# Alarm_project.net
KiCad netlist of a schematic drawn in EAGLE
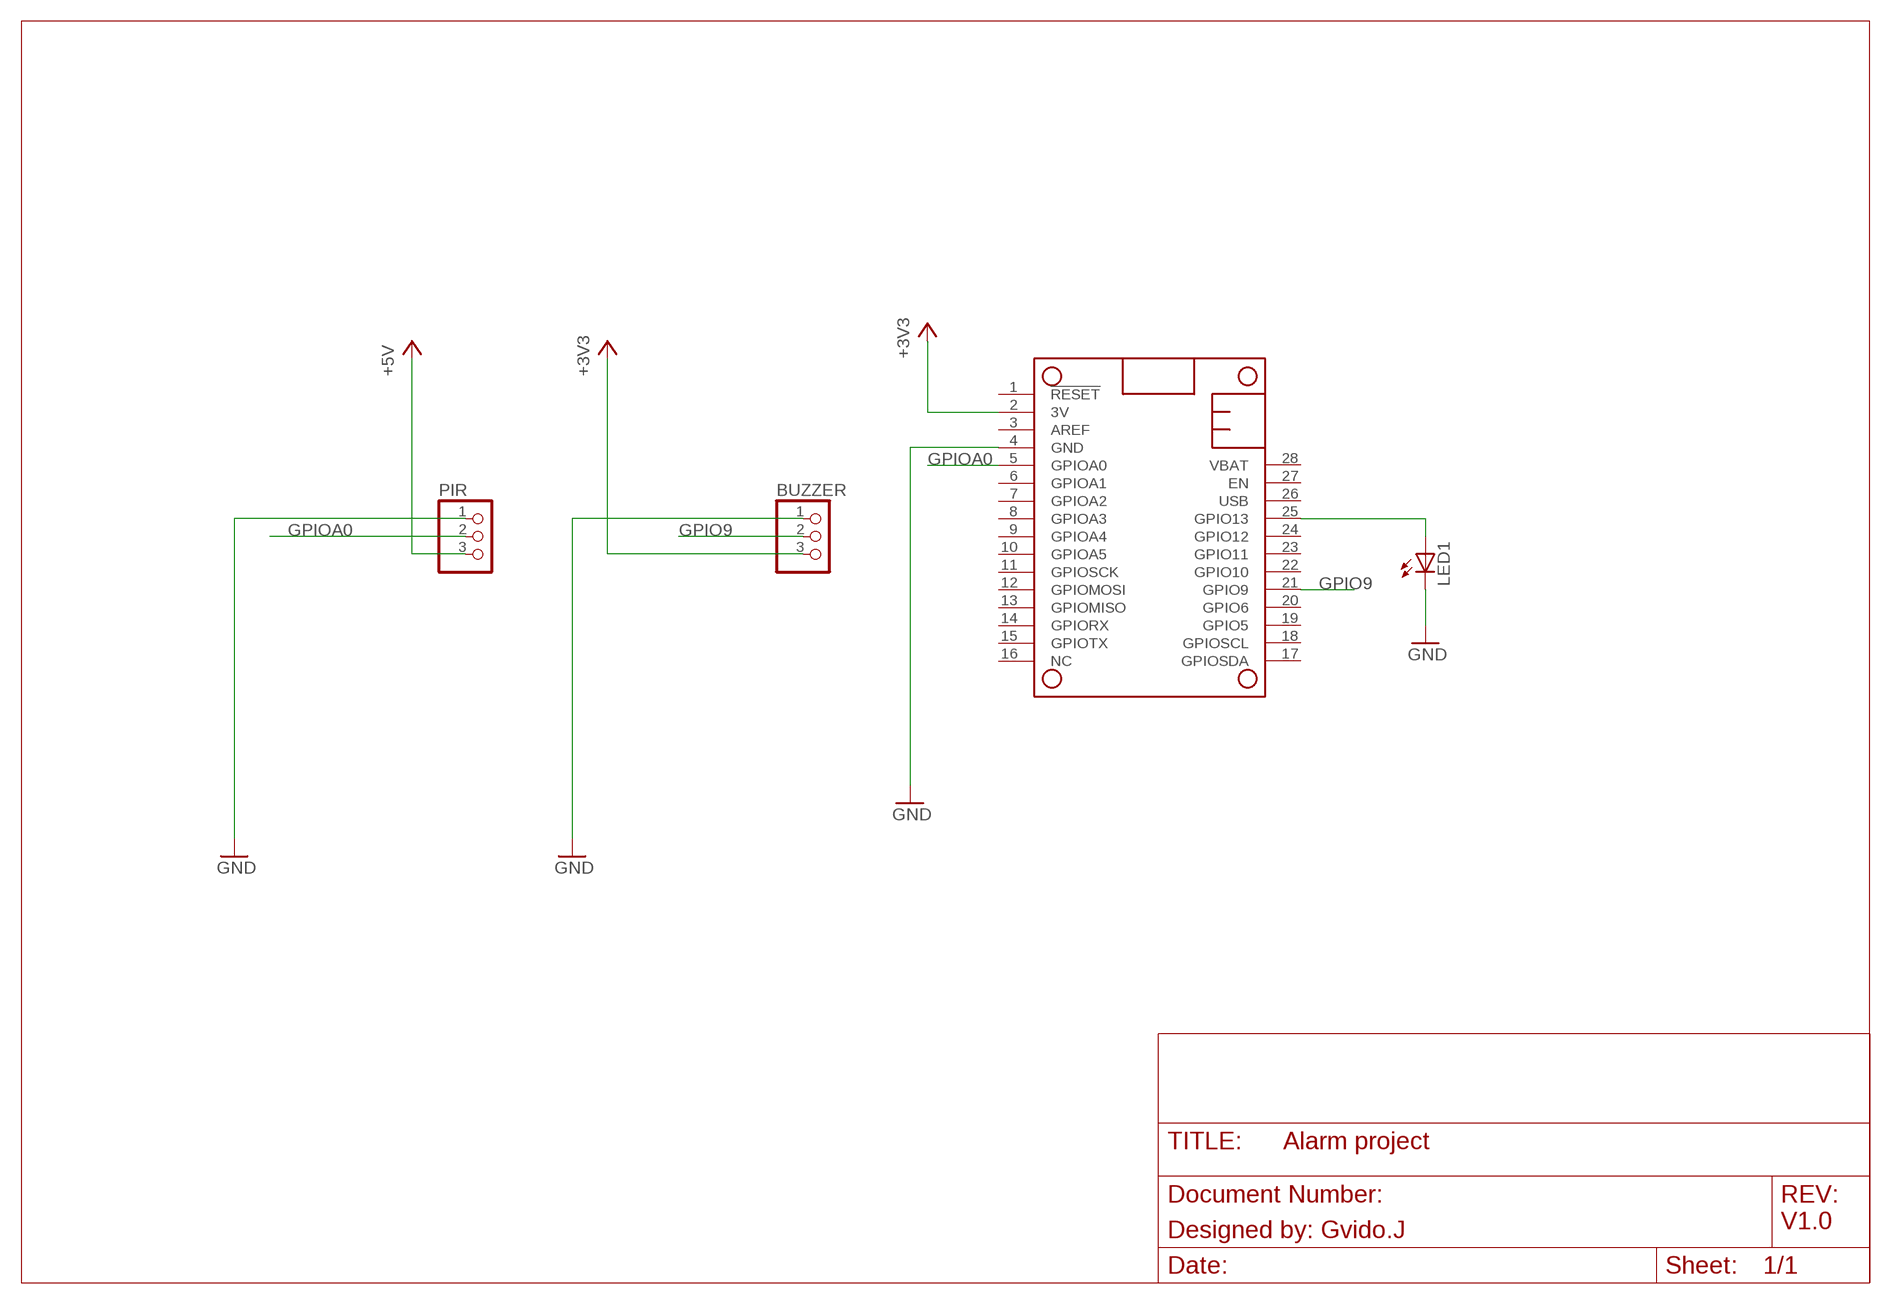
[diagram p0: schematic, sheet 1]

(export (version "E")
  (design (tool "Eeschema 10.0.6"))
  (components
    (comp (ref "BUZZER")
      (value "PINHD-1X3")
      (footprint "eagle-import:1X03")
      (libsource (lib "eagle-import") (part "PINHD-1X3"))
    )
    (comp (ref "LED1")
      (value "LED")
      (footprint "eagle-import:SMARTLED-TTW")
      (libsource (lib "eagle-import") (part "LED"))
    )
    (comp (ref "MS1")
      (value "FEATHERWING")
      (footprint "eagle-import:FEATHERWING")
      (libsource (lib "eagle-import") (part "FEATHERWING"))
    )
    (comp (ref "PIR")
      (value "PINHD-1X3")
      (footprint "eagle-import:1X03")
      (libsource (lib "eagle-import") (part "PINHD-1X3"))
    )
  )
  (nets
    (net (code "1") (name "+3V3") (class "Default")
      (node (ref "BUZZER") (pin "3") (pinfunction "3_3") (pintype "passive"))
      (node (ref "MS1") (pin "2") (pinfunction "3V_2") (pintype "power_in"))
    )
    (net (code "2") (name "+5V") (class "Default")
      (node (ref "PIR") (pin "3") (pinfunction "3_3") (pintype "passive"))
    )
    (net (code "3") (name "/GPIO9") (class "Default")
      (node (ref "BUZZER") (pin "2") (pinfunction "2_2") (pintype "passive"))
      (node (ref "MS1") (pin "21") (pinfunction "GPIO9_21") (pintype "bidirectional"))
    )
    (net (code "4") (name "/GPIOA0") (class "Default")
      (node (ref "MS1") (pin "5") (pinfunction "GPIOA0_5") (pintype "bidirectional"))
      (node (ref "PIR") (pin "2") (pinfunction "2_2") (pintype "passive"))
    )
    (net (code "5") (name "/USB") (class "Default")
      (node (ref "MS1") (pin "26") (pinfunction "USB_26") (pintype "power_in"))
    )
    (net (code "6") (name "/VBAT") (class "Default")
      (node (ref "MS1") (pin "28") (pinfunction "VBAT_28") (pintype "power_in"))
    )
    (net (code "7") (name "GND") (class "Default")
      (node (ref "BUZZER") (pin "1") (pinfunction "1_1") (pintype "passive"))
      (node (ref "LED1") (pin "C@1") (pinfunction "C_C@1") (pintype "passive"))
      (node (ref "MS1") (pin "4") (pinfunction "GND_4") (pintype "power_in"))
      (node (ref "PIR") (pin "1") (pinfunction "1_1") (pintype "passive"))
    )
    (net (code "8") (name "Net-(LED1-A)") (class "Default")
      (node (ref "LED1") (pin "A@1") (pinfunction "A_A@1") (pintype "passive"))
      (node (ref "MS1") (pin "25") (pinfunction "GPIO13_25") (pintype "bidirectional"))
    )
    (net (code "9") (name "unconnected-(MS1-AREF-Pad3)") (class "Default")
      (node (ref "MS1") (pin "3") (pinfunction "AREF_3") (pintype "passive"))
    )
    (net (code "10") (name "unconnected-(MS1-EN-Pad27)") (class "Default")
      (node (ref "MS1") (pin "27") (pinfunction "EN_27") (pintype "passive"))
    )
    (net (code "11") (name "unconnected-(MS1-GPIO5-Pad19)") (class "Default")
      (node (ref "MS1") (pin "19") (pinfunction "GPIO5_19") (pintype "bidirectional"))
    )
    (net (code "12") (name "unconnected-(MS1-GPIO6-Pad20)") (class "Default")
      (node (ref "MS1") (pin "20") (pinfunction "GPIO6_20") (pintype "bidirectional"))
    )
    (net (code "13") (name "unconnected-(MS1-GPIO10-Pad22)") (class "Default")
      (node (ref "MS1") (pin "22") (pinfunction "GPIO10_22") (pintype "bidirectional"))
    )
    (net (code "14") (name "unconnected-(MS1-GPIO11-Pad23)") (class "Default")
      (node (ref "MS1") (pin "23") (pinfunction "GPIO11_23") (pintype "bidirectional"))
    )
    (net (code "15") (name "unconnected-(MS1-GPIO12-Pad24)") (class "Default")
      (node (ref "MS1") (pin "24") (pinfunction "GPIO12_24") (pintype "bidirectional"))
    )
    (net (code "16") (name "unconnected-(MS1-GPIOA1-Pad6)") (class "Default")
      (node (ref "MS1") (pin "6") (pinfunction "GPIOA1_6") (pintype "bidirectional"))
    )
    (net (code "17") (name "unconnected-(MS1-GPIOA2-Pad7)") (class "Default")
      (node (ref "MS1") (pin "7") (pinfunction "GPIOA2_7") (pintype "bidirectional"))
    )
    (net (code "18") (name "unconnected-(MS1-GPIOA3-Pad8)") (class "Default")
      (node (ref "MS1") (pin "8") (pinfunction "GPIOA3_8") (pintype "bidirectional"))
    )
    (net (code "19") (name "unconnected-(MS1-GPIOA4-Pad9)") (class "Default")
      (node (ref "MS1") (pin "9") (pinfunction "GPIOA4_9") (pintype "bidirectional"))
    )
    (net (code "20") (name "unconnected-(MS1-GPIOA5-Pad10)") (class "Default")
      (node (ref "MS1") (pin "10") (pinfunction "GPIOA5_10") (pintype "bidirectional"))
    )
    (net (code "21") (name "unconnected-(MS1-GPIOMISO-Pad13)") (class "Default")
      (node (ref "MS1") (pin "13") (pinfunction "GPIOMISO_13") (pintype "bidirectional"))
    )
    (net (code "22") (name "unconnected-(MS1-GPIOMOSI-Pad12)") (class "Default")
      (node (ref "MS1") (pin "12") (pinfunction "GPIOMOSI_12") (pintype "bidirectional"))
    )
    (net (code "23") (name "unconnected-(MS1-GPIORX-Pad14)") (class "Default")
      (node (ref "MS1") (pin "14") (pinfunction "GPIORX_14") (pintype "bidirectional"))
    )
    (net (code "24") (name "unconnected-(MS1-GPIOSCK-Pad11)") (class "Default")
      (node (ref "MS1") (pin "11") (pinfunction "GPIOSCK_11") (pintype "bidirectional"))
    )
    (net (code "25") (name "unconnected-(MS1-GPIOSCL-Pad18)") (class "Default")
      (node (ref "MS1") (pin "18") (pinfunction "GPIOSCL_18") (pintype "bidirectional"))
    )
    (net (code "26") (name "unconnected-(MS1-GPIOSDA-Pad17)") (class "Default")
      (node (ref "MS1") (pin "17") (pinfunction "GPIOSDA_17") (pintype "bidirectional"))
    )
    (net (code "27") (name "unconnected-(MS1-GPIOTX-Pad15)") (class "Default")
      (node (ref "MS1") (pin "15") (pinfunction "GPIOTX_15") (pintype "bidirectional"))
    )
    (net (code "28") (name "unconnected-(MS1-NC-Pad16)") (class "Default")
      (node (ref "MS1") (pin "16") (pinfunction "NC_16") (pintype "passive"))
    )
    (net (code "29") (name "unconnected-(MS1-~{RESET}-Pad1)") (class "Default")
      (node (ref "MS1") (pin "1") (pinfunction "~{RESET}_1") (pintype "input"))
    )
  )
)
